# LilyPad-E-Sewing-Kit_v14.net
KiCad netlist of a schematic drawn in EAGLE
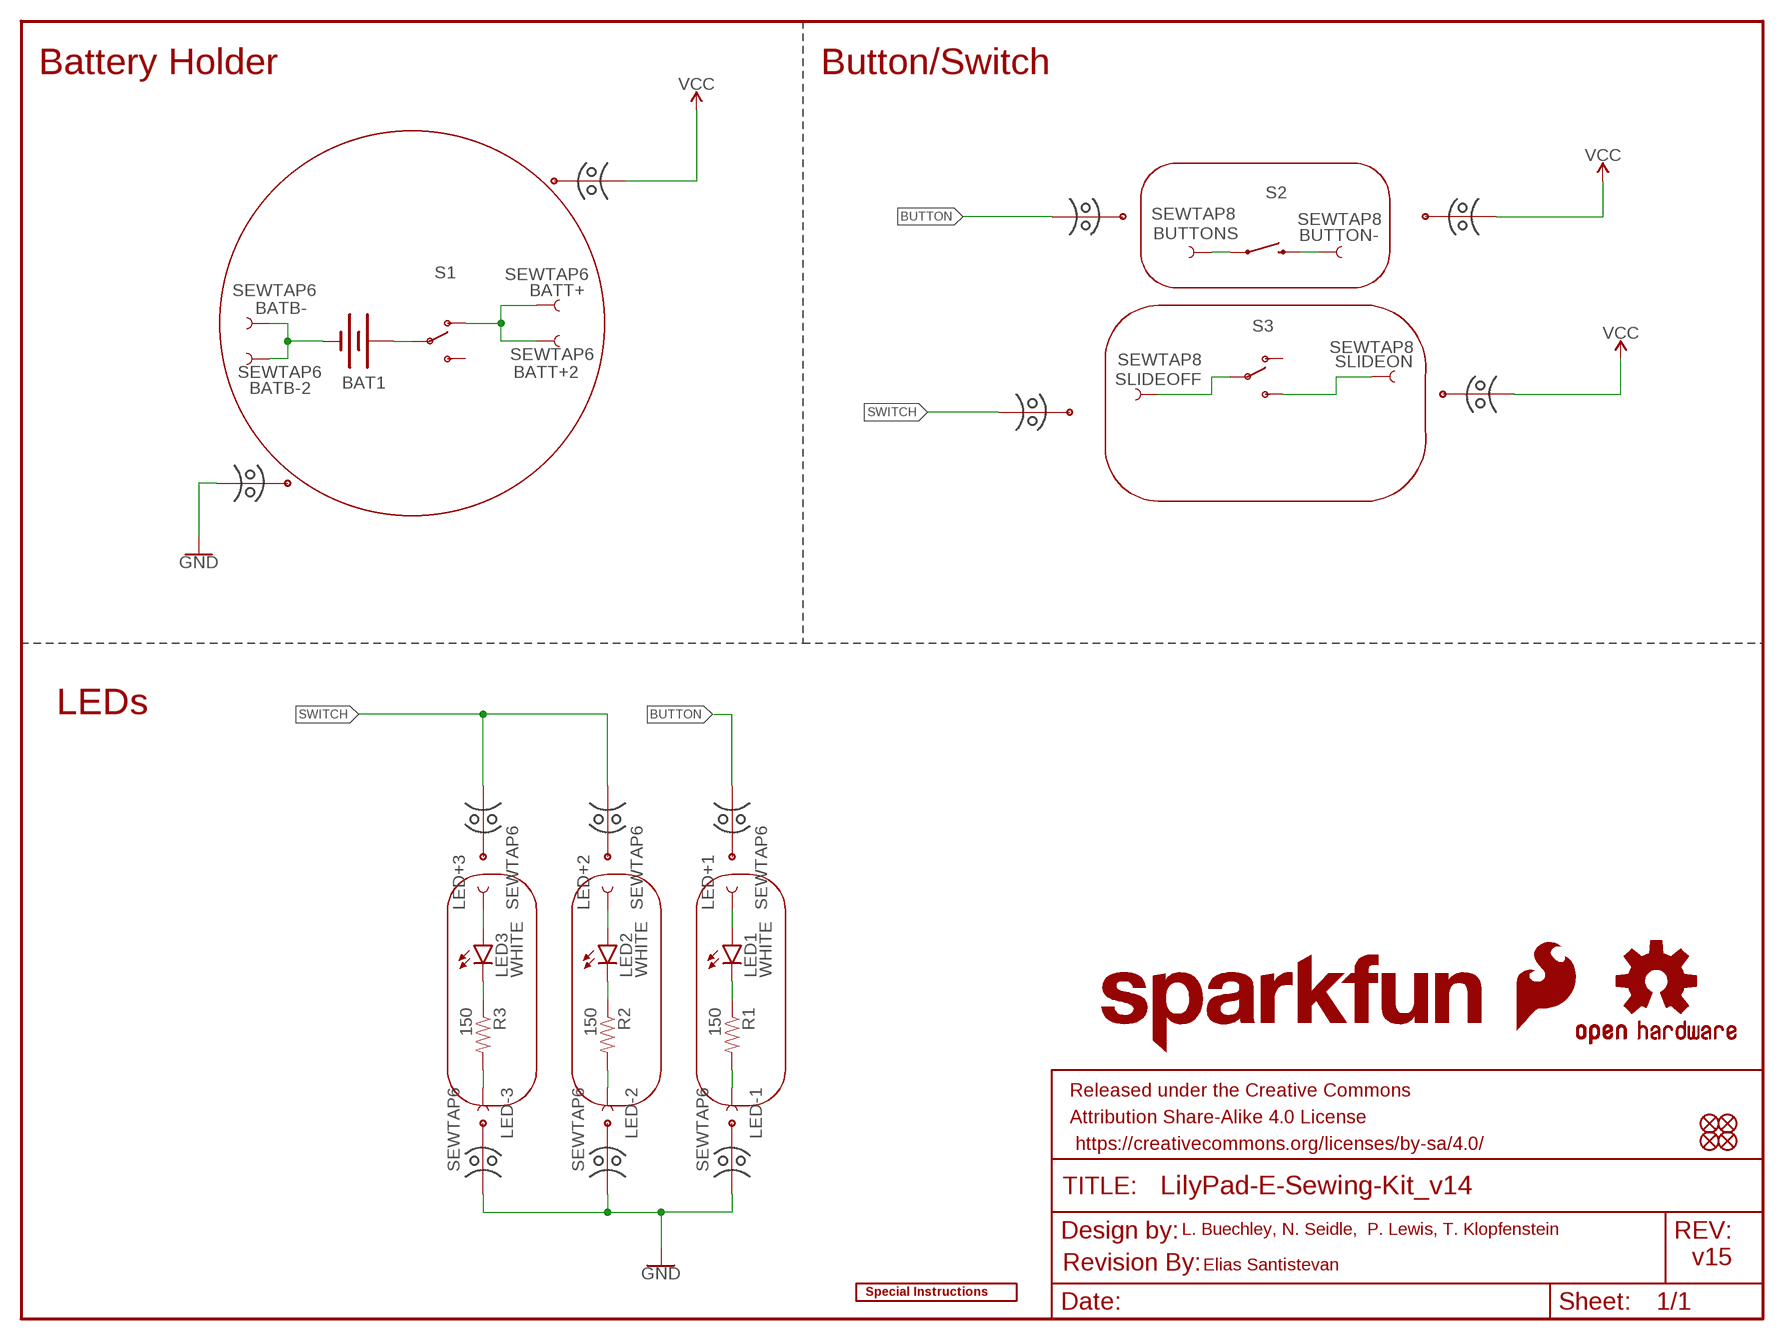
[diagram p0: schematic, sheet 1]

(export (version "E")
  (design (tool "Eeschema 10.0.6"))
  (components
    (comp (ref "BAT1")
      (value "20mm coincell")
      (footprint "eagle-import:BATTCON_20MM_4LEGS")
      (libsource (lib "eagle-import") (part "BATTERY20MM_4LEGS"))
    )
    (comp (ref "BATB-")
      (value "SEWTAP6")
      (footprint "eagle-import:PETAL-SMALL-2SIDE")
      (libsource (lib "eagle-import") (part "SEWTAP6"))
    )
    (comp (ref "BATB-2")
      (value "SEWTAP6")
      (footprint "eagle-import:PETAL-SMALL-2SIDE")
      (libsource (lib "eagle-import") (part "SEWTAP6"))
    )
    (comp (ref "BATT+")
      (value "SEWTAP6")
      (footprint "eagle-import:PETAL-SMALL-2SIDE")
      (libsource (lib "eagle-import") (part "SEWTAP6"))
    )
    (comp (ref "BATT+2")
      (value "SEWTAP6")
      (footprint "eagle-import:PETAL-SMALL-2SIDE")
      (libsource (lib "eagle-import") (part "SEWTAP6"))
    )
    (comp (ref "BUTTON-")
      (value "SEWTAP8")
      (footprint "eagle-import:PETAL-MEDIUM-2SIDE")
      (libsource (lib "eagle-import") (part "SEWTAP8"))
    )
    (comp (ref "BUTTONS")
      (value "SEWTAP8")
      (footprint "eagle-import:PETAL-MEDIUM-2SIDE")
      (libsource (lib "eagle-import") (part "SEWTAP8"))
    )
    (comp (ref "FD1")
      (value "FIDUCIALUFIDUCIAL")
      (footprint "eagle-import:MICRO-FIDUCIAL")
      (libsource (lib "eagle-import") (part "FIDUCIALUFIDUCIAL"))
    )
    (comp (ref "FD2")
      (value "FIDUCIALUFIDUCIAL")
      (footprint "eagle-import:MICRO-FIDUCIAL")
      (libsource (lib "eagle-import") (part "FIDUCIALUFIDUCIAL"))
    )
    (comp (ref "FD3")
      (value "FIDUCIALUFIDUCIAL")
      (footprint "eagle-import:MICRO-FIDUCIAL")
      (libsource (lib "eagle-import") (part "FIDUCIALUFIDUCIAL"))
    )
    (comp (ref "FD4")
      (value "FIDUCIALUFIDUCIAL")
      (footprint "eagle-import:MICRO-FIDUCIAL")
      (libsource (lib "eagle-import") (part "FIDUCIALUFIDUCIAL"))
    )
    (comp (ref "FRAME1")
      (value "FRAME-LETTER")
      (footprint "eagle-import:CREATIVE_COMMONS")
      (libsource (lib "eagle-import") (part "FRAME-LETTER"))
    )
    (comp (ref "LED+1")
      (value "SEWTAP6")
      (footprint "eagle-import:PETAL-SMALL-2SIDE")
      (libsource (lib "eagle-import") (part "SEWTAP6"))
    )
    (comp (ref "LED+2")
      (value "SEWTAP6")
      (footprint "eagle-import:PETAL-SMALL-2SIDE")
      (libsource (lib "eagle-import") (part "SEWTAP6"))
    )
    (comp (ref "LED+3")
      (value "SEWTAP6")
      (footprint "eagle-import:PETAL-SMALL-2SIDE")
      (libsource (lib "eagle-import") (part "SEWTAP6"))
    )
    (comp (ref "LED-1")
      (value "SEWTAP6")
      (footprint "eagle-import:PETAL-SMALL-2SIDE")
      (libsource (lib "eagle-import") (part "SEWTAP6"))
    )
    (comp (ref "LED-2")
      (value "SEWTAP6")
      (footprint "eagle-import:PETAL-SMALL-2SIDE")
      (libsource (lib "eagle-import") (part "SEWTAP6"))
    )
    (comp (ref "LED-3")
      (value "SEWTAP6")
      (footprint "eagle-import:PETAL-SMALL-2SIDE")
      (libsource (lib "eagle-import") (part "SEWTAP6"))
    )
    (comp (ref "LED1")
      (value "WHITE")
      (footprint "eagle-import:LED-1206")
      (libsource (lib "eagle-import") (part "LED-WHITE1206"))
    )
    (comp (ref "LED2")
      (value "WHITE")
      (footprint "eagle-import:LED-1206")
      (libsource (lib "eagle-import") (part "LED-WHITE1206"))
    )
    (comp (ref "LED3")
      (value "WHITE")
      (footprint "eagle-import:LED-1206")
      (libsource (lib "eagle-import") (part "LED-WHITE1206"))
    )
    (comp (ref "LOGO1")
      (value "SFE_LOGO_FLAME.1_INCH")
      (footprint "eagle-import:SFE_LOGO_FLAME_.1")
      (libsource (lib "eagle-import") (part "SFE_LOGO_FLAME.1_INCH"))
    )
    (comp (ref "LOGO2")
      (value "OSHW-LOGOS")
      (footprint "eagle-import:OSHW-LOGO-S")
      (libsource (lib "eagle-import") (part "OSHW-LOGOS"))
    )
    (comp (ref "LOGO3")
      (value "SFE_LOGO_NAME.1_INCH")
      (footprint "eagle-import:SFE_LOGO_NAME_.1")
      (libsource (lib "eagle-import") (part "SFE_LOGO_NAME.1_INCH"))
    )
    (comp (ref "MB+")
      (value "MOUSE-BITE-12_HOLES")
      (footprint "eagle-import:MOUST-BITE-1-(2_HOLES)")
      (libsource (lib "eagle-import") (part "MOUSE-BITE-12_HOLES"))
    )
    (comp (ref "MB-")
      (value "MOUSE-BITE-12_HOLES")
      (footprint "eagle-import:MOUST-BITE-1-(2_HOLES)")
      (libsource (lib "eagle-import") (part "MOUSE-BITE-12_HOLES"))
    )
    (comp (ref "MB1")
      (value "MOUSE-BITE-12_HOLES")
      (footprint "eagle-import:MOUST-BITE-1-(2_HOLES)")
      (libsource (lib "eagle-import") (part "MOUSE-BITE-12_HOLES"))
    )
    (comp (ref "MB2")
      (value "MOUSE-BITE-12_HOLES")
      (footprint "eagle-import:MOUST-BITE-1-(2_HOLES)")
      (libsource (lib "eagle-import") (part "MOUSE-BITE-12_HOLES"))
    )
    (comp (ref "MB3")
      (value "MOUSE-BITE-12_HOLES")
      (footprint "eagle-import:MOUST-BITE-1-(2_HOLES)")
      (libsource (lib "eagle-import") (part "MOUSE-BITE-12_HOLES"))
    )
    (comp (ref "MB4")
      (value "MOUSE-BITE-12_HOLES")
      (footprint "eagle-import:MOUST-BITE-1-(2_HOLES)")
      (libsource (lib "eagle-import") (part "MOUSE-BITE-12_HOLES"))
    )
    (comp (ref "MB5")
      (value "MOUSE-BITE-12_HOLES")
      (footprint "eagle-import:MOUST-BITE-1-(2_HOLES)")
      (libsource (lib "eagle-import") (part "MOUSE-BITE-12_HOLES"))
    )
    (comp (ref "MB6")
      (value "MOUSE-BITE-12_HOLES")
      (footprint "eagle-import:MOUST-BITE-1-(2_HOLES)")
      (libsource (lib "eagle-import") (part "MOUSE-BITE-12_HOLES"))
    )
    (comp (ref "MB7")
      (value "MOUSE-BITE-12_HOLES")
      (footprint "eagle-import:MOUST-BITE-1-(2_HOLES)")
      (libsource (lib "eagle-import") (part "MOUSE-BITE-12_HOLES"))
    )
    (comp (ref "MB8")
      (value "MOUSE-BITE-12_HOLES")
      (footprint "eagle-import:MOUST-BITE-1-(2_HOLES)")
      (libsource (lib "eagle-import") (part "MOUSE-BITE-12_HOLES"))
    )
    (comp (ref "MB9")
      (value "MOUSE-BITE-12_HOLES")
      (footprint "eagle-import:MOUST-BITE-1-(2_HOLES)")
      (libsource (lib "eagle-import") (part "MOUSE-BITE-12_HOLES"))
    )
    (comp (ref "MB10")
      (value "MOUSE-BITE-12_HOLES")
      (footprint "eagle-import:MOUST-BITE-1-(2_HOLES)")
      (libsource (lib "eagle-import") (part "MOUSE-BITE-12_HOLES"))
    )
    (comp (ref "R1")
      (value "150")
      (footprint "eagle-import:0603-RES")
      (libsource (lib "eagle-import") (part "150OHM-1/10W-1%(0603)"))
    )
    (comp (ref "R2")
      (value "150")
      (footprint "eagle-import:0603-RES")
      (libsource (lib "eagle-import") (part "150OHM-1/10W-1%(0603)"))
    )
    (comp (ref "R3")
      (value "150")
      (footprint "eagle-import:0603-RES")
      (libsource (lib "eagle-import") (part "150OHM-1/10W-1%(0603)"))
    )
    (comp (ref "S1")
      (value "S1")
      (footprint "eagle-import:AYZ0202")
      (libsource (lib "eagle-import") (part "SWITCH-SPDTSMD"))
    )
    (comp (ref "S2")
      (value "SWITCH-MOMENTARY-2SMD")
      (footprint "eagle-import:TACTILE-SWITCH-SMD")
      (libsource (lib "eagle-import") (part "SWITCH-MOMENTARY-2SMD"))
    )
    (comp (ref "S3")
      (value "S3")
      (footprint "eagle-import:AYZ0202")
      (libsource (lib "eagle-import") (part "SWITCH-SPDTSMD"))
    )
    (comp (ref "SLIDEOFF")
      (value "SEWTAP8")
      (footprint "eagle-import:PETAL-MEDIUM-2SIDE")
      (libsource (lib "eagle-import") (part "SEWTAP8"))
    )
    (comp (ref "SLIDEON")
      (value "SEWTAP8")
      (footprint "eagle-import:PETAL-MEDIUM-2SIDE")
      (libsource (lib "eagle-import") (part "SEWTAP8"))
    )
    (comp (ref "U$1")
      (value "REVISION")
      (footprint "eagle-import:REVISION")
      (libsource (lib "eagle-import") (part "REVISION"))
    )
    (comp (ref "U$9")
      (value "SPECIAL_INSTRUCTIONS-ORDERING")
      (footprint "eagle-import:ORDERING_INSTRUCTIONS")
      (libsource (lib "eagle-import") (part "SPECIAL_INSTRUCTIONS-ORDERING"))
    )
  )
  (nets
    (net (code "1") (name "BUTTON") (class "Default")
      (node (ref "BUTTONS") (pin "1") (pinfunction "1_1") (pintype "bidirectional"))
      (node (ref "LED+1") (pin "1") (pinfunction "1_1") (pintype "bidirectional"))
      (node (ref "LED1") (pin "A") (pinfunction "A_A") (pintype "passive"))
      (node (ref "MB3") (pin "P$1") (pinfunction "P$1_P$1") (pintype "bidirectional"))
      (node (ref "MB9") (pin "P$1") (pinfunction "P$1_P$1") (pintype "bidirectional"))
      (node (ref "S2") (pin "1") (pinfunction "1_1") (pintype "passive"))
    )
    (net (code "2") (name "GND") (class "Default")
      (node (ref "BAT1") (pin "NEGATIVE") (pinfunction "-_NEGATIVE") (pintype "power_in"))
      (node (ref "BATB-") (pin "1") (pinfunction "1_1") (pintype "bidirectional"))
      (node (ref "BATB-2") (pin "1") (pinfunction "1_1") (pintype "bidirectional"))
      (node (ref "LED-1") (pin "1") (pinfunction "1_1") (pintype "bidirectional"))
      (node (ref "LED-2") (pin "1") (pinfunction "1_1") (pintype "bidirectional"))
      (node (ref "LED-3") (pin "1") (pinfunction "1_1") (pintype "bidirectional"))
      (node (ref "MB-") (pin "P$1") (pinfunction "P$1_P$1") (pintype "bidirectional"))
      (node (ref "MB6") (pin "P$1") (pinfunction "P$1_P$1") (pintype "bidirectional"))
      (node (ref "MB7") (pin "P$1") (pinfunction "P$1_P$1") (pintype "bidirectional"))
      (node (ref "MB8") (pin "P$1") (pinfunction "P$1_P$1") (pintype "bidirectional"))
      (node (ref "R1") (pin "2") (pinfunction "2_2") (pintype "passive"))
      (node (ref "R2") (pin "2") (pinfunction "2_2") (pintype "passive"))
      (node (ref "R3") (pin "2") (pinfunction "2_2") (pintype "passive"))
    )
    (net (code "3") (name "Net-(LED1-PadC)") (class "Default")
      (node (ref "LED1") (pin "C") (pinfunction "C_C") (pintype "passive"))
      (node (ref "R1") (pin "1") (pinfunction "1_1") (pintype "passive"))
    )
    (net (code "4") (name "Net-(LED2-PadC)") (class "Default")
      (node (ref "LED2") (pin "C") (pinfunction "C_C") (pintype "passive"))
      (node (ref "R2") (pin "1") (pinfunction "1_1") (pintype "passive"))
    )
    (net (code "5") (name "Net-(LED3-PadC)") (class "Default")
      (node (ref "LED3") (pin "C") (pinfunction "C_C") (pintype "passive"))
      (node (ref "R3") (pin "1") (pinfunction "1_1") (pintype "passive"))
    )
    (net (code "6") (name "Net-(S1-P)") (class "Default")
      (node (ref "BAT1") (pin "POSITIVE@1") (pinfunction "+_POSITIVE@1") (pintype "power_in"))
      (node (ref "BAT1") (pin "POSITIVE@2") (pinfunction "+_POSITIVE@2") (pintype "power_in"))
      (node (ref "BAT1") (pin "POSITIVE@3") (pinfunction "+_POSITIVE@3") (pintype "power_in"))
      (node (ref "BAT1") (pin "POSITIVE@4") (pinfunction "+_POSITIVE@4") (pintype "power_in"))
      (node (ref "S1") (pin "2") (pinfunction "P_2") (pintype "passive"))
    )
    (net (code "7") (name "SWITCH") (class "Default")
      (node (ref "LED+2") (pin "1") (pinfunction "1_1") (pintype "bidirectional"))
      (node (ref "LED+3") (pin "1") (pinfunction "1_1") (pintype "bidirectional"))
      (node (ref "LED2") (pin "A") (pinfunction "A_A") (pintype "passive"))
      (node (ref "LED3") (pin "A") (pinfunction "A_A") (pintype "passive"))
      (node (ref "MB10") (pin "P$1") (pinfunction "P$1_P$1") (pintype "bidirectional"))
      (node (ref "MB4") (pin "P$1") (pinfunction "P$1_P$1") (pintype "bidirectional"))
      (node (ref "MB5") (pin "P$1") (pinfunction "P$1_P$1") (pintype "bidirectional"))
      (node (ref "S3") (pin "2") (pinfunction "P_2") (pintype "passive"))
      (node (ref "SLIDEOFF") (pin "1") (pinfunction "1_1") (pintype "bidirectional"))
    )
    (net (code "8") (name "VCC") (class "Default")
      (node (ref "BATT+") (pin "1") (pinfunction "1_1") (pintype "bidirectional"))
      (node (ref "BATT+2") (pin "1") (pinfunction "1_1") (pintype "bidirectional"))
      (node (ref "BUTTON-") (pin "1") (pinfunction "1_1") (pintype "bidirectional"))
      (node (ref "MB+") (pin "P$1") (pinfunction "P$1_P$1") (pintype "bidirectional"))
      (node (ref "MB1") (pin "P$1") (pinfunction "P$1_P$1") (pintype "bidirectional"))
      (node (ref "MB2") (pin "P$1") (pinfunction "P$1_P$1") (pintype "bidirectional"))
      (node (ref "S1") (pin "1") (pinfunction "O_1") (pintype "passive"))
      (node (ref "S2") (pin "3") (pinfunction "2_3") (pintype "passive"))
      (node (ref "S3") (pin "3") (pinfunction "S_3") (pintype "passive"))
      (node (ref "SLIDEON") (pin "1") (pinfunction "1_1") (pintype "bidirectional"))
    )
    (net (code "9") (name "unconnected-(S1-S-Pad3)") (class "Default")
      (node (ref "S1") (pin "3") (pinfunction "S_3") (pintype "passive"))
    )
    (net (code "10") (name "unconnected-(S3-O-Pad1)") (class "Default")
      (node (ref "S3") (pin "1") (pinfunction "O_1") (pintype "passive"))
    )
  )
)
